# Sheet3.net
KiCad netlist of a schematic drawn in Altium Designer
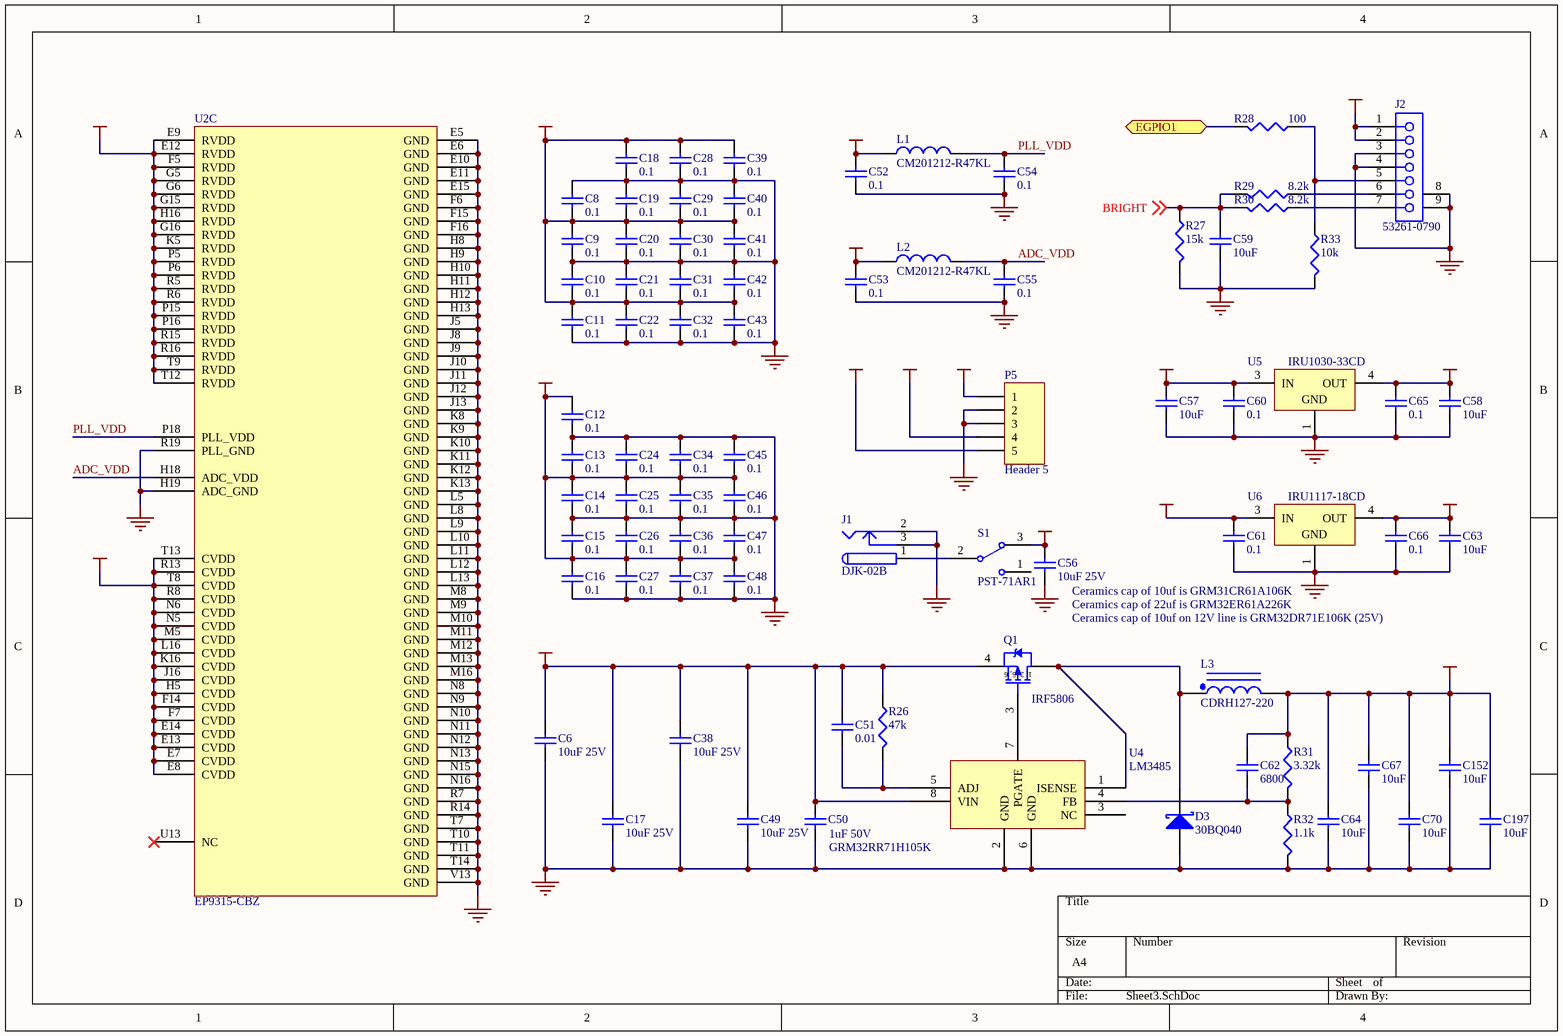
[diagram p0: Sheet3.SchDoc]

(export (version "E")
  (design (tool "Eeschema 10.0.6"))
  (components
    (comp (ref "C6")
      (value "10uF 25V")
      (footprint "1210")
      (description "Ceramic Chip Capacitor - Standard")
      (fields (field (name "PUBLISHER") "Altium Limited"))
      (libsource (lib "KEMET Chip Capacitor") (part "C1210"))
    )
    (comp (ref "C8")
      (value "0.1")
      (footprint "0603")
      (description "Ceramic Chip Capacitor - Standard")
      (fields (field (name "PUBLISHER") "Altium Limited"))
      (libsource (lib "KEMET Chip Capacitor") (part "C0603"))
    )
    (comp (ref "C9")
      (value "0.1")
      (footprint "0603")
      (description "Ceramic Chip Capacitor - Standard")
      (fields (field (name "PUBLISHER") "Altium Limited"))
      (libsource (lib "KEMET Chip Capacitor") (part "C0603"))
    )
    (comp (ref "C10")
      (value "0.1")
      (footprint "0603")
      (description "Ceramic Chip Capacitor - Standard")
      (fields (field (name "PUBLISHER") "Altium Limited"))
      (libsource (lib "KEMET Chip Capacitor") (part "C0603"))
    )
    (comp (ref "C11")
      (value "0.1")
      (footprint "0603")
      (description "Ceramic Chip Capacitor - Standard")
      (fields (field (name "PUBLISHER") "Altium Limited"))
      (libsource (lib "KEMET Chip Capacitor") (part "C0603"))
    )
    (comp (ref "C12")
      (value "0.1")
      (footprint "0603")
      (description "Ceramic Chip Capacitor - Standard")
      (fields (field (name "PUBLISHER") "Altium Limited"))
      (libsource (lib "KEMET Chip Capacitor") (part "C0603"))
    )
    (comp (ref "C13")
      (value "0.1")
      (footprint "0603")
      (description "Ceramic Chip Capacitor - Standard")
      (fields (field (name "PUBLISHER") "Altium Limited"))
      (libsource (lib "KEMET Chip Capacitor") (part "C0603"))
    )
    (comp (ref "C14")
      (value "0.1")
      (footprint "0603")
      (description "Ceramic Chip Capacitor - Standard")
      (fields (field (name "PUBLISHER") "Altium Limited"))
      (libsource (lib "KEMET Chip Capacitor") (part "C0603"))
    )
    (comp (ref "C15")
      (value "0.1")
      (footprint "0603")
      (description "Ceramic Chip Capacitor - Standard")
      (fields (field (name "PUBLISHER") "Altium Limited"))
      (libsource (lib "KEMET Chip Capacitor") (part "C0603"))
    )
    (comp (ref "C16")
      (value "0.1")
      (footprint "0603")
      (description "Ceramic Chip Capacitor - Standard")
      (fields (field (name "PUBLISHER") "Altium Limited"))
      (libsource (lib "KEMET Chip Capacitor") (part "C0603"))
    )
    (comp (ref "C17")
      (value "10uF 25V")
      (footprint "1210")
      (description "Ceramic Chip Capacitor - Standard")
      (fields (field (name "PUBLISHER") "Altium Limited"))
      (libsource (lib "KEMET Chip Capacitor") (part "C1210"))
    )
    (comp (ref "C18")
      (value "0.1")
      (footprint "0603")
      (description "Ceramic Chip Capacitor - Standard")
      (fields (field (name "PUBLISHER") "Altium Limited"))
      (libsource (lib "KEMET Chip Capacitor") (part "C0603"))
    )
    (comp (ref "C19")
      (value "0.1")
      (footprint "0603")
      (description "Ceramic Chip Capacitor - Standard")
      (fields (field (name "PUBLISHER") "Altium Limited"))
      (libsource (lib "KEMET Chip Capacitor") (part "C0603"))
    )
    (comp (ref "C20")
      (value "0.1")
      (footprint "0603")
      (description "Ceramic Chip Capacitor - Standard")
      (fields (field (name "PUBLISHER") "Altium Limited"))
      (libsource (lib "KEMET Chip Capacitor") (part "C0603"))
    )
    (comp (ref "C21")
      (value "0.1")
      (footprint "0603")
      (description "Ceramic Chip Capacitor - Standard")
      (fields (field (name "PUBLISHER") "Altium Limited"))
      (libsource (lib "KEMET Chip Capacitor") (part "C0603"))
    )
    (comp (ref "C22")
      (value "0.1")
      (footprint "0603")
      (description "Ceramic Chip Capacitor - Standard")
      (fields (field (name "PUBLISHER") "Altium Limited"))
      (libsource (lib "KEMET Chip Capacitor") (part "C0603"))
    )
    (comp (ref "C24")
      (value "0.1")
      (footprint "0603")
      (description "Ceramic Chip Capacitor - Standard")
      (fields (field (name "PUBLISHER") "Altium Limited"))
      (libsource (lib "KEMET Chip Capacitor") (part "C0603"))
    )
    (comp (ref "C25")
      (value "0.1")
      (footprint "0603")
      (description "Ceramic Chip Capacitor - Standard")
      (fields (field (name "PUBLISHER") "Altium Limited"))
      (libsource (lib "KEMET Chip Capacitor") (part "C0603"))
    )
    (comp (ref "C26")
      (value "0.1")
      (footprint "0603")
      (description "Ceramic Chip Capacitor - Standard")
      (fields (field (name "PUBLISHER") "Altium Limited"))
      (libsource (lib "KEMET Chip Capacitor") (part "C0603"))
    )
    (comp (ref "C27")
      (value "0.1")
      (footprint "0603")
      (description "Ceramic Chip Capacitor - Standard")
      (fields (field (name "PUBLISHER") "Altium Limited"))
      (libsource (lib "KEMET Chip Capacitor") (part "C0603"))
    )
    (comp (ref "C28")
      (value "0.1")
      (footprint "0603")
      (description "Ceramic Chip Capacitor - Standard")
      (fields (field (name "PUBLISHER") "Altium Limited"))
      (libsource (lib "KEMET Chip Capacitor") (part "C0603"))
    )
    (comp (ref "C29")
      (value "0.1")
      (footprint "0603")
      (description "Ceramic Chip Capacitor - Standard")
      (fields (field (name "PUBLISHER") "Altium Limited"))
      (libsource (lib "KEMET Chip Capacitor") (part "C0603"))
    )
    (comp (ref "C30")
      (value "0.1")
      (footprint "0603")
      (description "Ceramic Chip Capacitor - Standard")
      (fields (field (name "PUBLISHER") "Altium Limited"))
      (libsource (lib "KEMET Chip Capacitor") (part "C0603"))
    )
    (comp (ref "C31")
      (value "0.1")
      (footprint "0603")
      (description "Ceramic Chip Capacitor - Standard")
      (fields (field (name "PUBLISHER") "Altium Limited"))
      (libsource (lib "KEMET Chip Capacitor") (part "C0603"))
    )
    (comp (ref "C32")
      (value "0.1")
      (footprint "0603")
      (description "Ceramic Chip Capacitor - Standard")
      (fields (field (name "PUBLISHER") "Altium Limited"))
      (libsource (lib "KEMET Chip Capacitor") (part "C0603"))
    )
    (comp (ref "C34")
      (value "0.1")
      (footprint "0603")
      (description "Ceramic Chip Capacitor - Standard")
      (fields (field (name "PUBLISHER") "Altium Limited"))
      (libsource (lib "KEMET Chip Capacitor") (part "C0603"))
    )
    (comp (ref "C35")
      (value "0.1")
      (footprint "0603")
      (description "Ceramic Chip Capacitor - Standard")
      (fields (field (name "PUBLISHER") "Altium Limited"))
      (libsource (lib "KEMET Chip Capacitor") (part "C0603"))
    )
    (comp (ref "C36")
      (value "0.1")
      (footprint "0603")
      (description "Ceramic Chip Capacitor - Standard")
      (fields (field (name "PUBLISHER") "Altium Limited"))
      (libsource (lib "KEMET Chip Capacitor") (part "C0603"))
    )
    (comp (ref "C37")
      (value "0.1")
      (footprint "0603")
      (description "Ceramic Chip Capacitor - Standard")
      (fields (field (name "PUBLISHER") "Altium Limited"))
      (libsource (lib "KEMET Chip Capacitor") (part "C0603"))
    )
    (comp (ref "C38")
      (value "10uF 25V")
      (footprint "1210")
      (description "Ceramic Chip Capacitor - Standard")
      (fields (field (name "PUBLISHER") "Altium Limited"))
      (libsource (lib "KEMET Chip Capacitor") (part "C1210"))
    )
    (comp (ref "C39")
      (value "0.1")
      (footprint "0603")
      (description "Ceramic Chip Capacitor - Standard")
      (fields (field (name "PUBLISHER") "Altium Limited"))
      (libsource (lib "KEMET Chip Capacitor") (part "C0603"))
    )
    (comp (ref "C40")
      (value "0.1")
      (footprint "0603")
      (description "Ceramic Chip Capacitor - Standard")
      (fields (field (name "PUBLISHER") "Altium Limited"))
      (libsource (lib "KEMET Chip Capacitor") (part "C0603"))
    )
    (comp (ref "C41")
      (value "0.1")
      (footprint "0603")
      (description "Ceramic Chip Capacitor - Standard")
      (fields (field (name "PUBLISHER") "Altium Limited"))
      (libsource (lib "KEMET Chip Capacitor") (part "C0603"))
    )
    (comp (ref "C42")
      (value "0.1")
      (footprint "0603")
      (description "Ceramic Chip Capacitor - Standard")
      (fields (field (name "PUBLISHER") "Altium Limited"))
      (libsource (lib "KEMET Chip Capacitor") (part "C0603"))
    )
    (comp (ref "C43")
      (value "0.1")
      (footprint "0603")
      (description "Ceramic Chip Capacitor - Standard")
      (fields (field (name "PUBLISHER") "Altium Limited"))
      (libsource (lib "KEMET Chip Capacitor") (part "C0603"))
    )
    (comp (ref "C45")
      (value "0.1")
      (footprint "0603")
      (description "Ceramic Chip Capacitor - Standard")
      (fields (field (name "PUBLISHER") "Altium Limited"))
      (libsource (lib "KEMET Chip Capacitor") (part "C0603"))
    )
    (comp (ref "C46")
      (value "0.1")
      (footprint "0603")
      (description "Ceramic Chip Capacitor - Standard")
      (fields (field (name "PUBLISHER") "Altium Limited"))
      (libsource (lib "KEMET Chip Capacitor") (part "C0603"))
    )
    (comp (ref "C47")
      (value "0.1")
      (footprint "0603")
      (description "Ceramic Chip Capacitor - Standard")
      (fields (field (name "PUBLISHER") "Altium Limited"))
      (libsource (lib "KEMET Chip Capacitor") (part "C0603"))
    )
    (comp (ref "C48")
      (value "0.1")
      (footprint "0603")
      (description "Ceramic Chip Capacitor - Standard")
      (fields (field (name "PUBLISHER") "Altium Limited"))
      (libsource (lib "KEMET Chip Capacitor") (part "C0603"))
    )
    (comp (ref "C49")
      (value "10uF 25V")
      (footprint "1210")
      (description "Ceramic Chip Capacitor - Standard")
      (fields (field (name "PUBLISHER") "Altium Limited"))
      (libsource (lib "KEMET Chip Capacitor") (part "C1210"))
    )
    (comp (ref "C50")
      (value "GRM32RR71H105K")
      (footprint "1210")
      (description "Ceramic Chip Capacitor - Standard")
      (fields (field (name "ALTIUM_VALUE") "1uF 50V") (field (name "PUBLISHER") "Altium Limited"))
      (libsource (lib "KEMET Chip Capacitor") (part "C1210"))
    )
    (comp (ref "C51")
      (value "0.01")
      (footprint "0603")
      (description "Ceramic Chip Capacitor - Standard")
      (fields (field (name "PUBLISHER") "Altium Limited"))
      (libsource (lib "KEMET Chip Capacitor") (part "C0603"))
    )
    (comp (ref "C52")
      (value "0.1")
      (footprint "0603")
      (description "Ceramic Chip Capacitor - Standard")
      (fields (field (name "PUBLISHER") "Altium Limited"))
      (libsource (lib "KEMET Chip Capacitor") (part "C0603"))
    )
    (comp (ref "C53")
      (value "0.1")
      (footprint "0603")
      (description "Ceramic Chip Capacitor - Standard")
      (fields (field (name "PUBLISHER") "Altium Limited"))
      (libsource (lib "KEMET Chip Capacitor") (part "C0603"))
    )
    (comp (ref "C54")
      (value "0.1")
      (footprint "0603")
      (description "Ceramic Chip Capacitor - Standard")
      (fields (field (name "PUBLISHER") "Altium Limited"))
      (libsource (lib "KEMET Chip Capacitor") (part "C0603"))
    )
    (comp (ref "C55")
      (value "0.1")
      (footprint "0603")
      (description "Ceramic Chip Capacitor - Standard")
      (fields (field (name "PUBLISHER") "Altium Limited"))
      (libsource (lib "KEMET Chip Capacitor") (part "C0603"))
    )
    (comp (ref "C56")
      (value "10uF 25V")
      (footprint "1210")
      (description "Ceramic Chip Capacitor - Standard")
      (fields (field (name "PUBLISHER") "Altium Limited"))
      (libsource (lib "KEMET Chip Capacitor") (part "C1210"))
    )
    (comp (ref "C57")
      (value "10uF")
      (footprint "1206")
      (description "Ceramic Chip Capacitor - Standard")
      (fields (field (name "PUBLISHER") "Altium Limited"))
      (libsource (lib "KEMET Chip Capacitor") (part "C1206"))
    )
    (comp (ref "C58")
      (value "10uF")
      (footprint "1206")
      (description "Ceramic Chip Capacitor - Standard")
      (fields (field (name "PUBLISHER") "Altium Limited"))
      (libsource (lib "KEMET Chip Capacitor") (part "C1206"))
    )
    (comp (ref "C59")
      (value "10uF")
      (footprint "1206")
      (description "Ceramic Chip Capacitor - Standard")
      (fields (field (name "PUBLISHER") "Altium Limited"))
      (libsource (lib "KEMET Chip Capacitor") (part "C1206"))
    )
    (comp (ref "C60")
      (value "0.1")
      (footprint "0603")
      (description "Ceramic Chip Capacitor - Standard")
      (fields (field (name "PUBLISHER") "Altium Limited"))
      (libsource (lib "KEMET Chip Capacitor") (part "C0603"))
    )
    (comp (ref "C61")
      (value "0.1")
      (footprint "0603")
      (description "Ceramic Chip Capacitor - Standard")
      (fields (field (name "PUBLISHER") "Altium Limited"))
      (libsource (lib "KEMET Chip Capacitor") (part "C0603"))
    )
    (comp (ref "C62")
      (value "6800")
      (footprint "0603")
      (description "Ceramic Chip Capacitor - Standard")
      (fields (field (name "PUBLISHER") "Altium Limited"))
      (libsource (lib "KEMET Chip Capacitor") (part "C0603"))
    )
    (comp (ref "C63")
      (value "10uF")
      (footprint "1206")
      (description "Ceramic Chip Capacitor - Standard")
      (fields (field (name "PUBLISHER") "Altium Limited"))
      (libsource (lib "KEMET Chip Capacitor") (part "C1206"))
    )
    (comp (ref "C64")
      (value "10uF")
      (footprint "1206")
      (description "Ceramic Chip Capacitor - Standard")
      (fields (field (name "PUBLISHER") "Altium Limited"))
      (libsource (lib "KEMET Chip Capacitor") (part "C1206"))
    )
    (comp (ref "C65")
      (value "0.1")
      (footprint "0603")
      (description "Ceramic Chip Capacitor - Standard")
      (fields (field (name "PUBLISHER") "Altium Limited"))
      (libsource (lib "KEMET Chip Capacitor") (part "C0603"))
    )
    (comp (ref "C66")
      (value "0.1")
      (footprint "0603")
      (description "Ceramic Chip Capacitor - Standard")
      (fields (field (name "PUBLISHER") "Altium Limited"))
      (libsource (lib "KEMET Chip Capacitor") (part "C0603"))
    )
    (comp (ref "C67")
      (value "10uF")
      (footprint "1206")
      (description "Ceramic Chip Capacitor - Standard")
      (fields (field (name "PUBLISHER") "Altium Limited"))
      (libsource (lib "KEMET Chip Capacitor") (part "C1206"))
    )
    (comp (ref "C70")
      (value "10uF")
      (footprint "1206")
      (description "Ceramic Chip Capacitor - Standard")
      (fields (field (name "PUBLISHER") "Altium Limited"))
      (libsource (lib "KEMET Chip Capacitor") (part "C1206"))
    )
    (comp (ref "C152")
      (value "10uF")
      (footprint "1206")
      (description "Ceramic Chip Capacitor - Standard")
      (fields (field (name "PUBLISHER") "Altium Limited"))
      (libsource (lib "KEMET Chip Capacitor") (part "C1206"))
    )
    (comp (ref "C197")
      (value "10uF")
      (footprint "1206")
      (description "Ceramic Chip Capacitor - Standard")
      (fields (field (name "PUBLISHER") "Altium Limited"))
      (libsource (lib "KEMET Chip Capacitor") (part "C1206"))
    )
    (comp (ref "D3")
      (value "30BQ040")
      (footprint "DIODE SMC")
      (description "Schottky Rectifier")
      (fields (field (name "PUBLISHER") "Altium Limited"))
      (libsource (lib "IR Discrete Rectifier - Schottky") (part "10MQ060N"))
    )
    (comp (ref "J1")
      (value "DJK-02B")
      (footprint "DJK-02A")
      (description "2.5mm Power Plug")
      (libsource (lib "*") (part "DJK-02B"))
    )
    (comp (ref "J2")
      (value "53261-0790")
      (footprint "53261-07")
      (description "Molex 1.25 Wire to board")
      (libsource (lib "*") (part "53261-0790"))
    )
    (comp (ref "L1")
      (value "CM201212-R47KL")
      (footprint "INDC2012-0805")
      (description "Inductor")
      (fields (field (name "PUBLISHER") "Altium Limited"))
      (libsource (lib "Miscellaneous Devices") (part "Inductor"))
    )
    (comp (ref "L2")
      (value "CM201212-R47KL")
      (footprint "INDC2012-0805")
      (description "Inductor")
      (fields (field (name "PUBLISHER") "Altium Limited"))
      (libsource (lib "Miscellaneous Devices") (part "Inductor"))
    )
    (comp (ref "L3")
      (value "CDRH127-220")
      (footprint "CDRH127")
      (description "Sumida Power Inductor")
      (libsource (lib "*") (part "CDRH127"))
    )
    (comp (ref "P5")
      (value "Header 5")
      (footprint "HDR1X5")
      (description "Header, 5-Pin")
      (fields (field (name "PUBLISHER") "Altium Limited"))
      (libsource (lib "Miscellaneous Connectors") (part "Header 5"))
    )
    (comp (ref "Q1")
      (value "IRF5806")
      (footprint "Micro6")
      (description "HEXFET Power MOSFET")
      (libsource (lib "*") (part "IRF5806"))
    )
    (comp (ref "R26")
      (value "47k")
      (footprint "CR1608-0603")
      (description "Resistor")
      (fields (field (name "PUBLISHER") "Altium Limited"))
      (libsource (lib "Miscellaneous Devices") (part "Res3"))
    )
    (comp (ref "R27")
      (value "15k")
      (footprint "CR1608-0603")
      (description "Resistor")
      (fields (field (name "PUBLISHER") "Altium Limited"))
      (libsource (lib "Miscellaneous Devices") (part "Res3"))
    )
    (comp (ref "R28")
      (value "100")
      (footprint "CR1608-0603")
      (description "Resistor")
      (fields (field (name "Comment") "0") (field (name "PUBLISHER") "Altium Limited"))
      (libsource (lib "Miscellaneous Devices") (part "Res3"))
    )
    (comp (ref "R29")
      (value "8.2k")
      (footprint "CR1608-0603")
      (description "Resistor")
      (fields (field (name "Comment") "0") (field (name "PUBLISHER") "Altium Limited"))
      (libsource (lib "Miscellaneous Devices") (part "Res3"))
    )
    (comp (ref "R30")
      (value "8.2k")
      (footprint "CR1608-0603")
      (description "Resistor")
      (fields (field (name "PUBLISHER") "Altium Limited"))
      (libsource (lib "Miscellaneous Devices") (part "Res3"))
    )
    (comp (ref "R31")
      (value "3.32k")
      (footprint "CR1608-0603")
      (description "Resistor")
      (fields (field (name "Comment") "3.6k") (field (name "PUBLISHER") "Altium Limited"))
      (libsource (lib "Miscellaneous Devices") (part "Res3"))
    )
    (comp (ref "R32")
      (value "1.1k")
      (footprint "CR1608-0603")
      (description "Resistor")
      (fields (field (name "PUBLISHER") "Altium Limited"))
      (libsource (lib "Miscellaneous Devices") (part "Res3"))
    )
    (comp (ref "R33")
      (value "10k")
      (footprint "CR1608-0603")
      (description "Resistor")
      (fields (field (name "Comment") "0") (field (name "PUBLISHER") "Altium Limited"))
      (libsource (lib "Miscellaneous Devices") (part "Res3"))
    )
    (comp (ref "S1") (value "PST-71AR1") (footprint "PST-71AR1") (libsource (lib "*") (part "PST-71AR1")))
    (comp (ref "U2")
      (value "EP9315-CBZ")
      (footprint "BGA352x20")
      (description "32 Bit ARM920T Microcontroller with inegrated graphics, IDE, PCMCIA, Ethernet")
      (libsource (lib "Cirrus") (part "EP9315-CBZ"))
    )
    (comp (ref "U4")
      (value "LM3485")
      (footprint "MSOP8")
      (description "Hysteretic PFET Buck Controller")
      (libsource (lib "*") (part "LM3485"))
    )
    (comp (ref "U5")
      (value "IRU1030-33CD")
      (footprint "TO-252-2 (D-PAK)")
      (description "1A low dropout positive fixed regulator")
      (libsource (lib "MiscDev") (part "IRU1010"))
    )
    (comp (ref "U6")
      (value "IRU1117-18CD")
      (footprint "TO-252-2 (D-PAK)")
      (description "1A low dropout positive fixed regulator")
      (libsource (lib "MiscDev") (part "IRU1010"))
    )
  )
  (nets
    (net (code "1") (name "/ADC_VDD") (class "Default")
      (node (ref "C55") (pin "2") (pinfunction "2_2") (pintype "passive"))
      (node (ref "L2") (pin "2") (pinfunction "2_2") (pintype "passive"))
      (node (ref "U2") (pin "H18") (pinfunction "ADC_VDD_H18") (pintype "power_in"))
    )
    (net (code "2") (name "/EGPIO1") (class "Default")
      (node (ref "R28") (pin "2") (pinfunction "2_2") (pintype "passive"))
    )
    (net (code "3") (name "/PLL_VDD") (class "Default")
      (node (ref "C54") (pin "2") (pinfunction "2_2") (pintype "passive"))
      (node (ref "L1") (pin "2") (pinfunction "2_2") (pintype "passive"))
      (node (ref "U2") (pin "P18") (pinfunction "PLL_VDD_P18") (pintype "power_in"))
    )
    (net (code "4") (name "BRIGHT") (class "Default")
      (node (ref "C59") (pin "2") (pinfunction "2_2") (pintype "passive"))
      (node (ref "R27") (pin "1") (pinfunction "1_1") (pintype "passive"))
      (node (ref "R29") (pin "2") (pinfunction "2_2") (pintype "passive"))
      (node (ref "R30") (pin "2") (pinfunction "2_2") (pintype "passive"))
    )
    (net (code "5") (name "GND") (class "Default")
      (node (ref "C10") (pin "2") (pinfunction "2_2") (pintype "passive"))
      (node (ref "C11") (pin "1") (pinfunction "1_1") (pintype "passive"))
      (node (ref "C12") (pin "1") (pinfunction "1_1") (pintype "passive"))
      (node (ref "C13") (pin "2") (pinfunction "2_2") (pintype "passive"))
      (node (ref "C14") (pin "1") (pinfunction "1_1") (pintype "passive"))
      (node (ref "C15") (pin "2") (pinfunction "2_2") (pintype "passive"))
      (node (ref "C152") (pin "1") (pinfunction "1_1") (pintype "passive"))
      (node (ref "C16") (pin "1") (pinfunction "1_1") (pintype "passive"))
      (node (ref "C17") (pin "1") (pinfunction "1_1") (pintype "passive"))
      (node (ref "C18") (pin "1") (pinfunction "1_1") (pintype "passive"))
      (node (ref "C19") (pin "2") (pinfunction "2_2") (pintype "passive"))
      (node (ref "C197") (pin "1") (pinfunction "1_1") (pintype "passive"))
      (node (ref "C20") (pin "1") (pinfunction "1_1") (pintype "passive"))
      (node (ref "C21") (pin "2") (pinfunction "2_2") (pintype "passive"))
      (node (ref "C22") (pin "1") (pinfunction "1_1") (pintype "passive"))
      (node (ref "C24") (pin "2") (pinfunction "2_2") (pintype "passive"))
      (node (ref "C25") (pin "1") (pinfunction "1_1") (pintype "passive"))
      (node (ref "C26") (pin "2") (pinfunction "2_2") (pintype "passive"))
      (node (ref "C27") (pin "1") (pinfunction "1_1") (pintype "passive"))
      (node (ref "C28") (pin "1") (pinfunction "1_1") (pintype "passive"))
      (node (ref "C29") (pin "2") (pinfunction "2_2") (pintype "passive"))
      (node (ref "C30") (pin "1") (pinfunction "1_1") (pintype "passive"))
      (node (ref "C31") (pin "2") (pinfunction "2_2") (pintype "passive"))
      (node (ref "C32") (pin "1") (pinfunction "1_1") (pintype "passive"))
      (node (ref "C34") (pin "2") (pinfunction "2_2") (pintype "passive"))
      (node (ref "C35") (pin "1") (pinfunction "1_1") (pintype "passive"))
      (node (ref "C36") (pin "2") (pinfunction "2_2") (pintype "passive"))
      (node (ref "C37") (pin "1") (pinfunction "1_1") (pintype "passive"))
      (node (ref "C38") (pin "1") (pinfunction "1_1") (pintype "passive"))
      (node (ref "C39") (pin "1") (pinfunction "1_1") (pintype "passive"))
      (node (ref "C40") (pin "2") (pinfunction "2_2") (pintype "passive"))
      (node (ref "C41") (pin "1") (pinfunction "1_1") (pintype "passive"))
      (node (ref "C42") (pin "2") (pinfunction "2_2") (pintype "passive"))
      (node (ref "C43") (pin "1") (pinfunction "1_1") (pintype "passive"))
      (node (ref "C45") (pin "2") (pinfunction "2_2") (pintype "passive"))
      (node (ref "C46") (pin "1") (pinfunction "1_1") (pintype "passive"))
      (node (ref "C47") (pin "2") (pinfunction "2_2") (pintype "passive"))
      (node (ref "C48") (pin "1") (pinfunction "1_1") (pintype "passive"))
      (node (ref "C49") (pin "1") (pinfunction "1_1") (pintype "passive"))
      (node (ref "C50") (pin "1") (pinfunction "1_1") (pintype "passive"))
      (node (ref "C52") (pin "1") (pinfunction "1_1") (pintype "passive"))
      (node (ref "C53") (pin "1") (pinfunction "1_1") (pintype "passive"))
      (node (ref "C54") (pin "1") (pinfunction "1_1") (pintype "passive"))
      (node (ref "C55") (pin "1") (pinfunction "1_1") (pintype "passive"))
      (node (ref "C56") (pin "1") (pinfunction "1_1") (pintype "passive"))
      (node (ref "C57") (pin "1") (pinfunction "1_1") (pintype "passive"))
      (node (ref "C58") (pin "1") (pinfunction "1_1") (pintype "passive"))
      (node (ref "C59") (pin "1") (pinfunction "1_1") (pintype "passive"))
      (node (ref "C6") (pin "1") (pinfunction "1_1") (pintype "passive"))
      (node (ref "C60") (pin "1") (pinfunction "1_1") (pintype "passive"))
      (node (ref "C61") (pin "1") (pinfunction "1_1") (pintype "passive"))
      (node (ref "C63") (pin "1") (pinfunction "1_1") (pintype "passive"))
      (node (ref "C64") (pin "1") (pinfunction "1_1") (pintype "passive"))
      (node (ref "C65") (pin "1") (pinfunction "1_1") (pintype "passive"))
      (node (ref "C66") (pin "1") (pinfunction "1_1") (pintype "passive"))
      (node (ref "C67") (pin "1") (pinfunction "1_1") (pintype "passive"))
      (node (ref "C70") (pin "1") (pinfunction "1_1") (pintype "passive"))
      (node (ref "C8") (pin "2") (pinfunction "2_2") (pintype "passive"))
      (node (ref "C9") (pin "1") (pinfunction "1_1") (pintype "passive"))
      (node (ref "D3") (pin "1") (pinfunction "A_1") (pintype "passive"))
      (node (ref "J1") (pin "2") (pinfunction "2_2") (pintype "power_in"))
      (node (ref "J1") (pin "3") (pinfunction "3_3") (pintype "power_in"))
      (node (ref "J2") (pin "3") (pinfunction "3_3") (pintype "passive"))
      (node (ref "J2") (pin "4") (pinfunction "4_4") (pintype "passive"))
      (node (ref "J2") (pin "8") (pinfunction "8_8") (pintype "passive"))
      (node (ref "J2") (pin "9") (pinfunction "9_9") (pintype "passive"))
      (node (ref "P5") (pin "2") (pinfunction "2_2") (pintype "passive"))
      (node (ref "P5") (pin "3") (pinfunction "3_3") (pintype "passive"))
      (node (ref "R27") (pin "2") (pinfunction "2_2") (pintype "passive"))
      (node (ref "R32") (pin "2") (pinfunction "2_2") (pintype "passive"))
      (node (ref "R33") (pin "2") (pinfunction "2_2") (pintype "passive"))
      (node (ref "U2") (pin "E10") (pinfunction "GND_E10") (pintype "power_in"))
      (node (ref "U2") (pin "E11") (pinfunction "GND_E11") (pintype "power_in"))
      (node (ref "U2") (pin "E15") (pinfunction "GND_E15") (pintype "power_in"))
      (node (ref "U2") (pin "E5") (pinfunction "GND_E5") (pintype "power_in"))
      (node (ref "U2") (pin "E6") (pinfunction "GND_E6") (pintype "power_in"))
      (node (ref "U2") (pin "F15") (pinfunction "GND_F15") (pintype "power_in"))
      (node (ref "U2") (pin "F16") (pinfunction "GND_F16") (pintype "power_in"))
      (node (ref "U2") (pin "F6") (pinfunction "GND_F6") (pintype "power_in"))
      (node (ref "U2") (pin "H10") (pinfunction "GND_H10") (pintype "power_in"))
      (node (ref "U2") (pin "H11") (pinfunction "GND_H11") (pintype "power_in"))
      (node (ref "U2") (pin "H12") (pinfunction "GND_H12") (pintype "power_in"))
      (node (ref "U2") (pin "H13") (pinfunction "GND_H13") (pintype "power_in"))
      (node (ref "U2") (pin "H19") (pinfunction "ADC_GND_H19") (pintype "power_in"))
      (node (ref "U2") (pin "H8") (pinfunction "GND_H8") (pintype "power_in"))
      (node (ref "U2") (pin "H9") (pinfunction "GND_H9") (pintype "power_in"))
      (node (ref "U2") (pin "J10") (pinfunction "GND_J10") (pintype "power_in"))
      (node (ref "U2") (pin "J11") (pinfunction "GND_J11") (pintype "power_in"))
      (node (ref "U2") (pin "J12") (pinfunction "GND_J12") (pintype "power_in"))
      (node (ref "U2") (pin "J13") (pinfunction "GND_J13") (pintype "power_in"))
      (node (ref "U2") (pin "J5") (pinfunction "GND_J5") (pintype "power_in"))
      (node (ref "U2") (pin "J8") (pinfunction "GND_J8") (pintype "power_in"))
      (node (ref "U2") (pin "J9") (pinfunction "GND_J9") (pintype "power_in"))
      (node (ref "U2") (pin "K10") (pinfunction "GND_K10") (pintype "power_in"))
      (node (ref "U2") (pin "K11") (pinfunction "GND_K11") (pintype "power_in"))
      (node (ref "U2") (pin "K12") (pinfunction "GND_K12") (pintype "power_in"))
      (node (ref "U2") (pin "K13") (pinfunction "GND_K13") (pintype "power_in"))
      (node (ref "U2") (pin "K8") (pinfunction "GND_K8") (pintype "power_in"))
      (node (ref "U2") (pin "K9") (pinfunction "GND_K9") (pintype "power_in"))
      (node (ref "U2") (pin "L10") (pinfunction "GND_L10") (pintype "power_in"))
      (node (ref "U2") (pin "L11") (pinfunction "GND_L11") (pintype "power_in"))
      (node (ref "U2") (pin "L12") (pinfunction "GND_L12") (pintype "power_in"))
      (node (ref "U2") (pin "L13") (pinfunction "GND_L13") (pintype "power_in"))
      (node (ref "U2") (pin "L5") (pinfunction "GND_L5") (pintype "power_in"))
      (node (ref "U2") (pin "L8") (pinfunction "GND_L8") (pintype "power_in"))
      (node (ref "U2") (pin "L9") (pinfunction "GND_L9") (pintype "power_in"))
      (node (ref "U2") (pin "M10") (pinfunction "GND_M10") (pintype "power_in"))
      (node (ref "U2") (pin "M11") (pinfunction "GND_M11") (pintype "power_in"))
      (node (ref "U2") (pin "M12") (pinfunction "GND_M12") (pintype "power_in"))
      (node (ref "U2") (pin "M13") (pinfunction "GND_M13") (pintype "power_in"))
      (node (ref "U2") (pin "M16") (pinfunction "GND_M16") (pintype "power_in"))
      (node (ref "U2") (pin "M8") (pinfunction "GND_M8") (pintype "power_in"))
      (node (ref "U2") (pin "M9") (pinfunction "GND_M9") (pintype "power_in"))
      (node (ref "U2") (pin "N10") (pinfunction "GND_N10") (pintype "power_in"))
      (node (ref "U2") (pin "N11") (pinfunction "GND_N11") (pintype "power_in"))
      (node (ref "U2") (pin "N12") (pinfunction "GND_N12") (pintype "power_in"))
      (node (ref "U2") (pin "N13") (pinfunction "GND_N13") (pintype "power_in"))
      (node (ref "U2") (pin "N15") (pinfunction "GND_N15") (pintype "power_in"))
      (node (ref "U2") (pin "N16") (pinfunction "GND_N16") (pintype "power_in"))
      (node (ref "U2") (pin "N8") (pinfunction "GND_N8") (pintype "power_in"))
      (node (ref "U2") (pin "N9") (pinfunction "GND_N9") (pintype "power_in"))
      (node (ref "U2") (pin "R14") (pinfunction "GND_R14") (pintype "power_in"))
      (node (ref "U2") (pin "R19") (pinfunction "PLL_GND_R19") (pintype "power_in"))
      (node (ref "U2") (pin "R7") (pinfunction "GND_R7") (pintype "power_in"))
      (node (ref "U2") (pin "T10") (pinfunction "GND_T10") (pintype "power_in"))
      (node (ref "U2") (pin "T11") (pinfunction "GND_T11") (pintype "power_in"))
      (node (ref "U2") (pin "T14") (pinfunction "GND_T14") (pintype "power_in"))
      (node (ref "U2") (pin "T7") (pinfunction "GND_T7") (pintype "power_in"))
      (node (ref "U2") (pin "V13") (pinfunction "GND_V13") (pintype "power_in"))
      (node (ref "U4") (pin "2") (pinfunction "GND_2") (pintype "passive"))
      (node (ref "U4") (pin "6") (pinfunction "GND_6") (pintype "passive"))
      (node (ref "U5") (pin "1") (pinfunction "GND_1") (pintype "power_in"))
      (node (ref "U6") (pin "1") (pinfunction "GND_1") (pintype "power_in"))
    )
    (net (code "6") (name "Net-(D3-K)") (class "Default")
      (node (ref "D3") (pin "2") (pinfunction "K_2") (pintype "passive"))
      (node (ref "L3") (pin "1") (pinfunction "1_1") (pintype "passive"))
      (node (ref "Q1") (pin "1") (pinfunction "D_1") (pintype "passive"))
      (node (ref "Q1") (pin "2") (pinfunction "D_2") (pintype "passive"))
      (node (ref "Q1") (pin "5") (pinfunction "D_5") (pintype "passive"))
      (node (ref "Q1") (pin "6") (pinfunction "D_6") (pintype "passive"))
      (node (ref "U4") (pin "1") (pinfunction "ISENSE_1") (pintype "passive"))
    )
    (net (code "7") (name "Net-(J1-Pad1)") (class "Default")
      (node (ref "J1") (pin "1") (pinfunction "1_1") (pintype "power_in"))
      (node (ref "S1") (pin "2") (pinfunction "2_2") (pintype "passive"))
    )
    (net (code "8") (name "Net-(J2-Pad5)") (class "Default")
      (node (ref "J2") (pin "5") (pinfunction "5_5") (pintype "passive"))
      (node (ref "R28") (pin "1") (pinfunction "1_1") (pintype "passive"))
      (node (ref "R33") (pin "1") (pinfunction "1_1") (pintype "passive"))
    )
    (net (code "9") (name "Net-(J2-Pad6)") (class "Default")
      (node (ref "J2") (pin "6") (pinfunction "6_6") (pintype "passive"))
      (node (ref "R29") (pin "1") (pinfunction "1_1") (pintype "passive"))
    )
    (net (code "10") (name "Net-(J2-Pad7)") (class "Default")
      (node (ref "J2") (pin "7") (pinfunction "7_7") (pintype "passive"))
      (node (ref "R30") (pin "1") (pinfunction "1_1") (pintype "passive"))
    )
    (net (code "11") (name "Net-(Q1-G)") (class "Default")
      (node (ref "Q1") (pin "3") (pinfunction "G_3") (pintype "passive"))
      (node (ref "U4") (pin "7") (pinfunction "PGATE_7") (pintype "passive"))
    )
    (net (code "12") (name "Net-(U4-ADJ)") (class "Default")
      (node (ref "C51") (pin "1") (pinfunction "1_1") (pintype "passive"))
      (node (ref "R26") (pin "2") (pinfunction "2_2") (pintype "passive"))
      (node (ref "U4") (pin "5") (pinfunction "ADJ_5") (pintype "passive"))
    )
    (net (code "13") (name "Net-(U4-FB)") (class "Default")
      (node (ref "C62") (pin "1") (pinfunction "1_1") (pintype "passive"))
      (node (ref "R31") (pin "2") (pinfunction "2_2") (pintype "passive"))
      (node (ref "R32") (pin "1") (pinfunction "1_1") (pintype "passive"))
      (node (ref "U4") (pin "4") (pinfunction "FB_4") (pintype "passive"))
    )
    (net (code "14") (name "VCC5V0") (class "Default")
      (node (ref "C152") (pin "2") (pinfunction "2_2") (pintype "passive"))
      (node (ref "C197") (pin "2") (pinfunction "2_2") (pintype "passive"))
      (node (ref "C57") (pin "2") (pinfunction "2_2") (pintype "passive"))
      (node (ref "C60") (pin "2") (pinfunction "2_2") (pintype "passive"))
      (node (ref "C62") (pin "2") (pinfunction "2_2") (pintype "passive"))
      (node (ref "C64") (pin "2") (pinfunction "2_2") (pintype "passive"))
      (node (ref "C67") (pin "2") (pinfunction "2_2") (pintype "passive"))
      (node (ref "C70") (pin "2") (pinfunction "2_2") (pintype "passive"))
      (node (ref "L3") (pin "2") (pinfunction "2_2") (pintype "passive"))
      (node (ref "P5") (pin "4") (pinfunction "4_4") (pintype "passive"))
      (node (ref "R31") (pin "1") (pinfunction "1_1") (pintype "passive"))
      (node (ref "U5") (pin "3") (pinfunction "IN_3") (pintype "power_in"))
    )
    (net (code "15") (name "VCC12") (class "Default")
      (node (ref "C17") (pin "2") (pinfunction "2_2") (pintype "passive"))
      (node (ref "C38") (pin "2") (pinfunction "2_2") (pintype "passive"))
      (node (ref "C49") (pin "2") (pinfunction "2_2") (pintype "passive"))
      (node (ref "C50") (pin "2") (pinfunction "2_2") (pintype "passive"))
      (node (ref "C51") (pin "2") (pinfunction "2_2") (pintype "passive"))
      (node (ref "C56") (pin "2") (pinfunction "2_2") (pintype "passive"))
      (node (ref "C6") (pin "2") (pinfunction "2_2") (pintype "passive"))
      (node (ref "J2") (pin "1") (pinfunction "1_1") (pintype "passive"))
      (node (ref "J2") (pin "2") (pinfunction "2_2") (pintype "passive"))
      (node (ref "P5") (pin "1") (pinfunction "1_1") (pintype "passive"))
      (node (ref "Q1") (pin "4") (pinfunction "S_4") (pintype "passive"))
      (node (ref "R26") (pin "1") (pinfunction "1_1") (pintype "passive"))
      (node (ref "S1") (pin "3") (pinfunction "3_3") (pintype "passive"))
      (node (ref "U4") (pin "8") (pinfunction "VIN_8") (pintype "passive"))
    )
    (net (code "16") (name "VCCCORE") (class "Default")
      (node (ref "C12") (pin "2") (pinfunction "2_2") (pintype "passive"))
      (node (ref "C13") (pin "1") (pinfunction "1_1") (pintype "passive"))
      (node (ref "C14") (pin "2") (pinfunction "2_2") (pintype "passive"))
      (node (ref "C15") (pin "1") (pinfunction "1_1") (pintype "passive"))
      (node (ref "C16") (pin "2") (pinfunction "2_2") (pintype "passive"))
      (node (ref "C24") (pin "1") (pinfunction "1_1") (pintype "passive"))
      (node (ref "C25") (pin "2") (pinfunction "2_2") (pintype "passive"))
      (node (ref "C26") (pin "1") (pinfunction "1_1") (pintype "passive"))
      (node (ref "C27") (pin "2") (pinfunction "2_2") (pintype "passive"))
      (node (ref "C34") (pin "1") (pinfunction "1_1") (pintype "passive"))
      (node (ref "C35") (pin "2") (pinfunction "2_2") (pintype "passive"))
      (node (ref "C36") (pin "1") (pinfunction "1_1") (pintype "passive"))
      (node (ref "C37") (pin "2") (pinfunction "2_2") (pintype "passive"))
      (node (ref "C45") (pin "1") (pinfunction "1_1") (pintype "passive"))
      (node (ref "C46") (pin "2") (pinfunction "2_2") (pintype "passive"))
      (node (ref "C47") (pin "1") (pinfunction "1_1") (pintype "passive"))
      (node (ref "C48") (pin "2") (pinfunction "2_2") (pintype "passive"))
      (node (ref "C52") (pin "2") (pinfunction "2_2") (pintype "passive"))
      (node (ref "C63") (pin "2") (pinfunction "2_2") (pintype "passive"))
      (node (ref "C66") (pin "2") (pinfunction "2_2") (pintype "passive"))
      (node (ref "L1") (pin "1") (pinfunction "1_1") (pintype "passive"))
      (node (ref "U2") (pin "E13") (pinfunction "CVDD_E13") (pintype "power_in"))
      (node (ref "U2") (pin "E14") (pinfunction "CVDD_E14") (pintype "power_in"))
      (node (ref "U2") (pin "E7") (pinfunction "CVDD_E7") (pintype "power_in"))
      (node (ref "U2") (pin "E8") (pinfunction "CVDD_E8") (pintype "power_in"))
      (node (ref "U2") (pin "F14") (pinfunction "CVDD_F14") (pintype "power_in"))
      (node (ref "U2") (pin "F7") (pinfunction "CVDD_F7") (pintype "power_in"))
      (node (ref "U2") (pin "H5") (pinfunction "CVDD_H5") (pintype "power_in"))
      (node (ref "U2") (pin "J16") (pinfunction "CVDD_J16") (pintype "power_in"))
      (node (ref "U2") (pin "K16") (pinfunction "CVDD_K16") (pintype "power_in"))
      (node (ref "U2") (pin "L16") (pinfunction "CVDD_L16") (pintype "power_in"))
      (node (ref "U2") (pin "M5") (pinfunction "CVDD_M5") (pintype "power_in"))
      (node (ref "U2") (pin "N5") (pinfunction "CVDD_N5") (pintype "power_in"))
      (node (ref "U2") (pin "N6") (pinfunction "CVDD_N6") (pintype "power_in"))
      (node (ref "U2") (pin "R13") (pinfunction "CVDD_R13") (pintype "power_in"))
      (node (ref "U2") (pin "R8") (pinfunction "CVDD_R8") (pintype "power_in"))
      (node (ref "U2") (pin "T13") (pinfunction "CVDD_T13") (pintype "power_in"))
      (node (ref "U2") (pin "T8") (pinfunction "CVDD_T8") (pintype "power_in"))
      (node (ref "U6") (pin "4") (pinfunction "OUT_4") (pintype "power_in"))
    )
    (net (code "17") (name "VCCIO") (class "Default")
      (node (ref "C10") (pin "1") (pinfunction "1_1") (pintype "passive"))
      (node (ref "C11") (pin "2") (pinfunction "2_2") (pintype "passive"))
      (node (ref "C18") (pin "2") (pinfunction "2_2") (pintype "passive"))
      (node (ref "C19") (pin "1") (pinfunction "1_1") (pintype "passive"))
      (node (ref "C20") (pin "2") (pinfunction "2_2") (pintype "passive"))
      (node (ref "C21") (pin "1") (pinfunction "1_1") (pintype "passive"))
      (node (ref "C22") (pin "2") (pinfunction "2_2") (pintype "passive"))
      (node (ref "C28") (pin "2") (pinfunction "2_2") (pintype "passive"))
      (node (ref "C29") (pin "1") (pinfunction "1_1") (pintype "passive"))
      (node (ref "C30") (pin "2") (pinfunction "2_2") (pintype "passive"))
      (node (ref "C31") (pin "1") (pinfunction "1_1") (pintype "passive"))
      (node (ref "C32") (pin "2") (pinfunction "2_2") (pintype "passive"))
      (node (ref "C39") (pin "2") (pinfunction "2_2") (pintype "passive"))
      (node (ref "C40") (pin "1") (pinfunction "1_1") (pintype "passive"))
      (node (ref "C41") (pin "2") (pinfunction "2_2") (pintype "passive"))
      (node (ref "C42") (pin "1") (pinfunction "1_1") (pintype "passive"))
      (node (ref "C43") (pin "2") (pinfunction "2_2") (pintype "passive"))
      (node (ref "C53") (pin "2") (pinfunction "2_2") (pintype "passive"))
      (node (ref "C58") (pin "2") (pinfunction "2_2") (pintype "passive"))
      (node (ref "C61") (pin "2") (pinfunction "2_2") (pintype "passive"))
      (node (ref "C65") (pin "2") (pinfunction "2_2") (pintype "passive"))
      (node (ref "C8") (pin "1") (pinfunction "1_1") (pintype "passive"))
      (node (ref "C9") (pin "2") (pinfunction "2_2") (pintype "passive"))
      (node (ref "L2") (pin "1") (pinfunction "1_1") (pintype "passive"))
      (node (ref "P5") (pin "5") (pinfunction "5_5") (pintype "passive"))
      (node (ref "U2") (pin "E12") (pinfunction "RVDD_E12") (pintype "power_in"))
      (node (ref "U2") (pin "E9") (pinfunction "RVDD_E9") (pintype "power_in"))
      (node (ref "U2") (pin "F5") (pinfunction "RVDD_F5") (pintype "power_in"))
      (node (ref "U2") (pin "G15") (pinfunction "RVDD_G15") (pintype "power_in"))
      (node (ref "U2") (pin "G16") (pinfunction "RVDD_G16") (pintype "power_in"))
      (node (ref "U2") (pin "G5") (pinfunction "RVDD_G5") (pintype "power_in"))
      (node (ref "U2") (pin "G6") (pinfunction "RVDD_G6") (pintype "power_in"))
      (node (ref "U2") (pin "H16") (pinfunction "RVDD_H16") (pintype "power_in"))
      (node (ref "U2") (pin "K5") (pinfunction "RVDD_K5") (pintype "power_in"))
      (node (ref "U2") (pin "P15") (pinfunction "RVDD_P15") (pintype "power_in"))
      (node (ref "U2") (pin "P16") (pinfunction "RVDD_P16") (pintype "power_in"))
      (node (ref "U2") (pin "P5") (pinfunction "RVDD_P5") (pintype "power_in"))
      (node (ref "U2") (pin "P6") (pinfunction "RVDD_P6") (pintype "power_in"))
      (node (ref "U2") (pin "R15") (pinfunction "RVDD_R15") (pintype "power_in"))
      (node (ref "U2") (pin "R16") (pinfunction "RVDD_R16") (pintype "power_in"))
      (node (ref "U2") (pin "R5") (pinfunction "RVDD_R5") (pintype "power_in"))
      (node (ref "U2") (pin "R6") (pinfunction "RVDD_R6") (pintype "power_in"))
      (node (ref "U2") (pin "T12") (pinfunction "RVDD_T12") (pintype "power_in"))
      (node (ref "U2") (pin "T9") (pinfunction "RVDD_T9") (pintype "power_in"))
      (node (ref "U5") (pin "4") (pinfunction "OUT_4") (pintype "power_in"))
      (node (ref "U6") (pin "3") (pinfunction "IN_3") (pintype "power_in"))
    )
    (net (code "18") (name "unconnected-(S1-Pad1)") (class "Default")
      (node (ref "S1") (pin "1") (pinfunction "1_1") (pintype "passive"))
    )
    (net (code "19") (name "unconnected-(U2C-NC-PadU13)") (class "Default")
      (node (ref "U2") (pin "U13") (pinfunction "NC_U13") (pintype "passive+no_connect"))
    )
    (net (code "20") (name "unconnected-(U4-NC-Pad3)") (class "Default")
      (node (ref "U4") (pin "3") (pinfunction "NC_3") (pintype "passive"))
    )
  )
)
